# Line_Tracker.net
KiCad netlist of a schematic drawn in Altium Designer
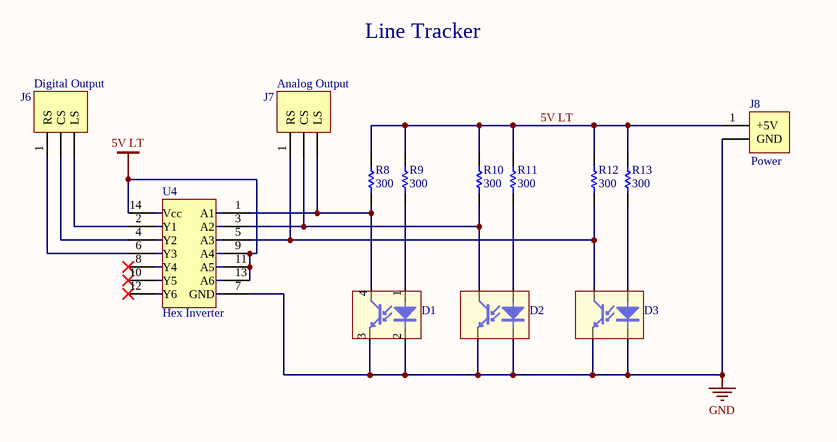
[diagram p0: Line Tracker.SchDoc]

(export (version "E")
  (design (tool "Eeschema 10.0.6"))
  (components
    (comp (ref "D1")
      (value "Optoisolator(custom)")
      (footprint "FTPNT_OPTOISOLATOR")
      (description "SENSOR OPTO TRANS 15MM REFL PCB")
      (fields (field (name "PUBLISHER") "Altium Limited"))
      (libsource (lib "Sensors_Schem") (part "Optoisolator1"))
    )
    (comp (ref "D2")
      (value "Optoisolator(custom)")
      (footprint "FTPNT_OPTOISOLATOR")
      (description "SENSOR OPTO TRANS 15MM REFL PCB")
      (fields (field (name "PUBLISHER") "Altium Limited"))
      (libsource (lib "") (part "Optoisolator1_1"))
    )
    (comp (ref "D3")
      (value "Optoisolator(custom)")
      (footprint "FTPNT_OPTOISOLATOR")
      (description "SENSOR OPTO TRANS 15MM REFL PCB")
      (fields (field (name "PUBLISHER") "Altium Limited"))
      (libsource (lib "") (part "Optoisolator1_1"))
    )
    (comp (ref "J6")
      (value "Digital Output")
      (footprint "HDR1X3")
      (description "CONN HEADER VERT 3POS .100 TIN")
      (fields (field (name "PUBLISHER") "Altium Limited"))
      (libsource (lib "Miscellaneous Connectors") (part "Header 3"))
    )
    (comp (ref "J7")
      (value "Analog Output")
      (footprint "HDR1X3")
      (description "CONN HEADER VERT 3POS .100 TIN")
      (fields (field (name "PUBLISHER") "Altium Limited"))
      (libsource (lib "Miscellaneous Connectors") (part "Header 3"))
    )
    (comp (ref "J8")
      (value "Power")
      (footprint "HDR1X2")
      (description "CONN HEADER VERT 2POS .100 TIN")
      (fields (field (name "PUBLISHER") "Altium Limited"))
      (libsource (lib "Miscellaneous Connectors") (part "Header 2"))
    )
    (comp (ref "R8")
      (value "300")
      (footprint "FTPNT_RESISTORS")
      (description "RES 300 OHM 1/4W 1% 1206 SMD")
      (fields (field (name "Comment") "Res1") (field (name "PUBLISHER") "Altium Limited"))
      (libsource (lib "Sensors_SchematicLib") (part "Res1"))
    )
    (comp (ref "R9")
      (value "300")
      (footprint "FTPNT_RESISTORS")
      (description "RES 300 OHM 1/4W 1% 1206 SMD")
      (fields (field (name "Comment") "Res1") (field (name "PUBLISHER") "Altium Limited"))
      (libsource (lib "Sensors_SchematicLib") (part "Res1"))
    )
    (comp (ref "R10")
      (value "300")
      (footprint "FTPNT_RESISTORS")
      (description "RES 300 OHM 1/4W 1% 1206 SMD")
      (fields (field (name "Comment") "Res1") (field (name "PUBLISHER") "Altium Limited"))
      (libsource (lib "Sensors_SchematicLib") (part "Res1"))
    )
    (comp (ref "R11")
      (value "300")
      (footprint "FTPNT_RESISTORS")
      (description "RES 300 OHM 1/4W 1% 1206 SMD")
      (fields (field (name "Comment") "Res1") (field (name "PUBLISHER") "Altium Limited"))
      (libsource (lib "Sensors_SchematicLib") (part "Res1"))
    )
    (comp (ref "R12")
      (value "300")
      (footprint "FTPNT_RESISTORS")
      (description "RES 300 OHM 1/4W 1% 1206 SMD")
      (fields (field (name "Comment") "Res1") (field (name "PUBLISHER") "Altium Limited"))
      (libsource (lib "Sensors_SchematicLib") (part "Res1"))
    )
    (comp (ref "R13")
      (value "300")
      (footprint "FTPNT_RESISTORS")
      (description "RES 300 OHM 1/4W 1% 1206 SMD")
      (fields (field (name "Comment") "Res1") (field (name "PUBLISHER") "Altium Limited"))
      (libsource (lib "Sensors_SchematicLib") (part "Res1"))
    )
    (comp (ref "U4")
      (value "Hex Inverter")
      (footprint "FTPNT_HEXINVERTER")
      (description "IC TRIGGER HEX INVERT 14-SOIC")
      (fields (field (name "PUBLISHER") "Altium Limited"))
      (libsource (lib "Miscellaneous Connectors") (part "Header 7X2A"))
    )
  )
  (nets
    (net (code "1") (name "5V LT") (class "Default")
      (node (ref "J8") (pin "1") (pinfunction "+5V_1") (pintype "passive"))
      (node (ref "R10") (pin "2") (pinfunction "2_2") (pintype "passive"))
      (node (ref "R11") (pin "2") (pinfunction "2_2") (pintype "passive"))
      (node (ref "R12") (pin "2") (pinfunction "2_2") (pintype "passive"))
      (node (ref "R13") (pin "2") (pinfunction "2_2") (pintype "passive"))
      (node (ref "R8") (pin "2") (pinfunction "2_2") (pintype "passive"))
      (node (ref "R9") (pin "2") (pinfunction "2_2") (pintype "passive"))
      (node (ref "U4") (pin "11") (pinfunction "A5_11") (pintype "passive"))
      (node (ref "U4") (pin "13") (pinfunction "A6_13") (pintype "passive"))
      (node (ref "U4") (pin "14") (pinfunction "Vcc_14") (pintype "passive"))
      (node (ref "U4") (pin "9") (pinfunction "A4_9") (pintype "passive"))
    )
    (net (code "2") (name "GND") (class "Default")
      (node (ref "D1") (pin "2") (pinfunction "K_2") (pintype "passive"))
      (node (ref "D1") (pin "3") (pinfunction "E_3") (pintype "passive"))
      (node (ref "D2") (pin "2") (pinfunction "K_2") (pintype "passive"))
      (node (ref "D2") (pin "3") (pinfunction "E_3") (pintype "passive"))
      (node (ref "D3") (pin "2") (pinfunction "K_2") (pintype "passive"))
      (node (ref "D3") (pin "3") (pinfunction "E_3") (pintype "passive"))
      (node (ref "J8") (pin "2") (pinfunction "GND_2") (pintype "passive"))
      (node (ref "U4") (pin "7") (pinfunction "GND_7") (pintype "passive"))
    )
    (net (code "3") (name "Net-(D1-A)") (class "Default")
      (node (ref "D1") (pin "1") (pinfunction "A_1") (pintype "passive"))
      (node (ref "R9") (pin "1") (pinfunction "1_1") (pintype "passive"))
    )
    (net (code "4") (name "Net-(D1-C)") (class "Default")
      (node (ref "D1") (pin "4") (pinfunction "C_4") (pintype "passive"))
      (node (ref "J7") (pin "3") (pinfunction "LS_3") (pintype "passive"))
      (node (ref "R8") (pin "1") (pinfunction "1_1") (pintype "passive"))
      (node (ref "U4") (pin "1") (pinfunction "A1_1") (pintype "passive"))
    )
    (net (code "5") (name "Net-(D2-A)") (class "Default")
      (node (ref "D2") (pin "1") (pinfunction "A_1") (pintype "passive"))
      (node (ref "R11") (pin "1") (pinfunction "1_1") (pintype "passive"))
    )
    (net (code "6") (name "Net-(D2-C)") (class "Default")
      (node (ref "D2") (pin "4") (pinfunction "C_4") (pintype "passive"))
      (node (ref "J7") (pin "2") (pinfunction "CS_2") (pintype "passive"))
      (node (ref "R10") (pin "1") (pinfunction "1_1") (pintype "passive"))
      (node (ref "U4") (pin "3") (pinfunction "A2_3") (pintype "passive"))
    )
    (net (code "7") (name "Net-(D3-A)") (class "Default")
      (node (ref "D3") (pin "1") (pinfunction "A_1") (pintype "passive"))
      (node (ref "R13") (pin "1") (pinfunction "1_1") (pintype "passive"))
    )
    (net (code "8") (name "Net-(D3-C)") (class "Default")
      (node (ref "D3") (pin "4") (pinfunction "C_4") (pintype "passive"))
      (node (ref "J7") (pin "1") (pinfunction "RS_1") (pintype "passive"))
      (node (ref "R12") (pin "1") (pinfunction "1_1") (pintype "passive"))
      (node (ref "U4") (pin "5") (pinfunction "A3_5") (pintype "passive"))
    )
    (net (code "9") (name "Net-(J6-CS)") (class "Default")
      (node (ref "J6") (pin "2") (pinfunction "CS_2") (pintype "passive"))
      (node (ref "U4") (pin "4") (pinfunction "Y2_4") (pintype "passive"))
    )
    (net (code "10") (name "Net-(J6-LS)") (class "Default")
      (node (ref "J6") (pin "3") (pinfunction "LS_3") (pintype "passive"))
      (node (ref "U4") (pin "2") (pinfunction "Y1_2") (pintype "passive"))
    )
    (net (code "11") (name "Net-(J6-RS)") (class "Default")
      (node (ref "J6") (pin "1") (pinfunction "RS_1") (pintype "passive"))
      (node (ref "U4") (pin "6") (pinfunction "Y3_6") (pintype "passive"))
    )
    (net (code "12") (name "unconnected-(U4-Y4-Pad8)") (class "Default")
      (node (ref "U4") (pin "8") (pinfunction "Y4_8") (pintype "passive+no_connect"))
    )
    (net (code "13") (name "unconnected-(U4-Y5-Pad10)") (class "Default")
      (node (ref "U4") (pin "10") (pinfunction "Y5_10") (pintype "passive+no_connect"))
    )
    (net (code "14") (name "unconnected-(U4-Y6-Pad12)") (class "Default")
      (node (ref "U4") (pin "12") (pinfunction "Y6_12") (pintype "passive+no_connect"))
    )
  )
)
